# schema_electrica.net
KiCad netlist of a schematic drawn in EAGLE
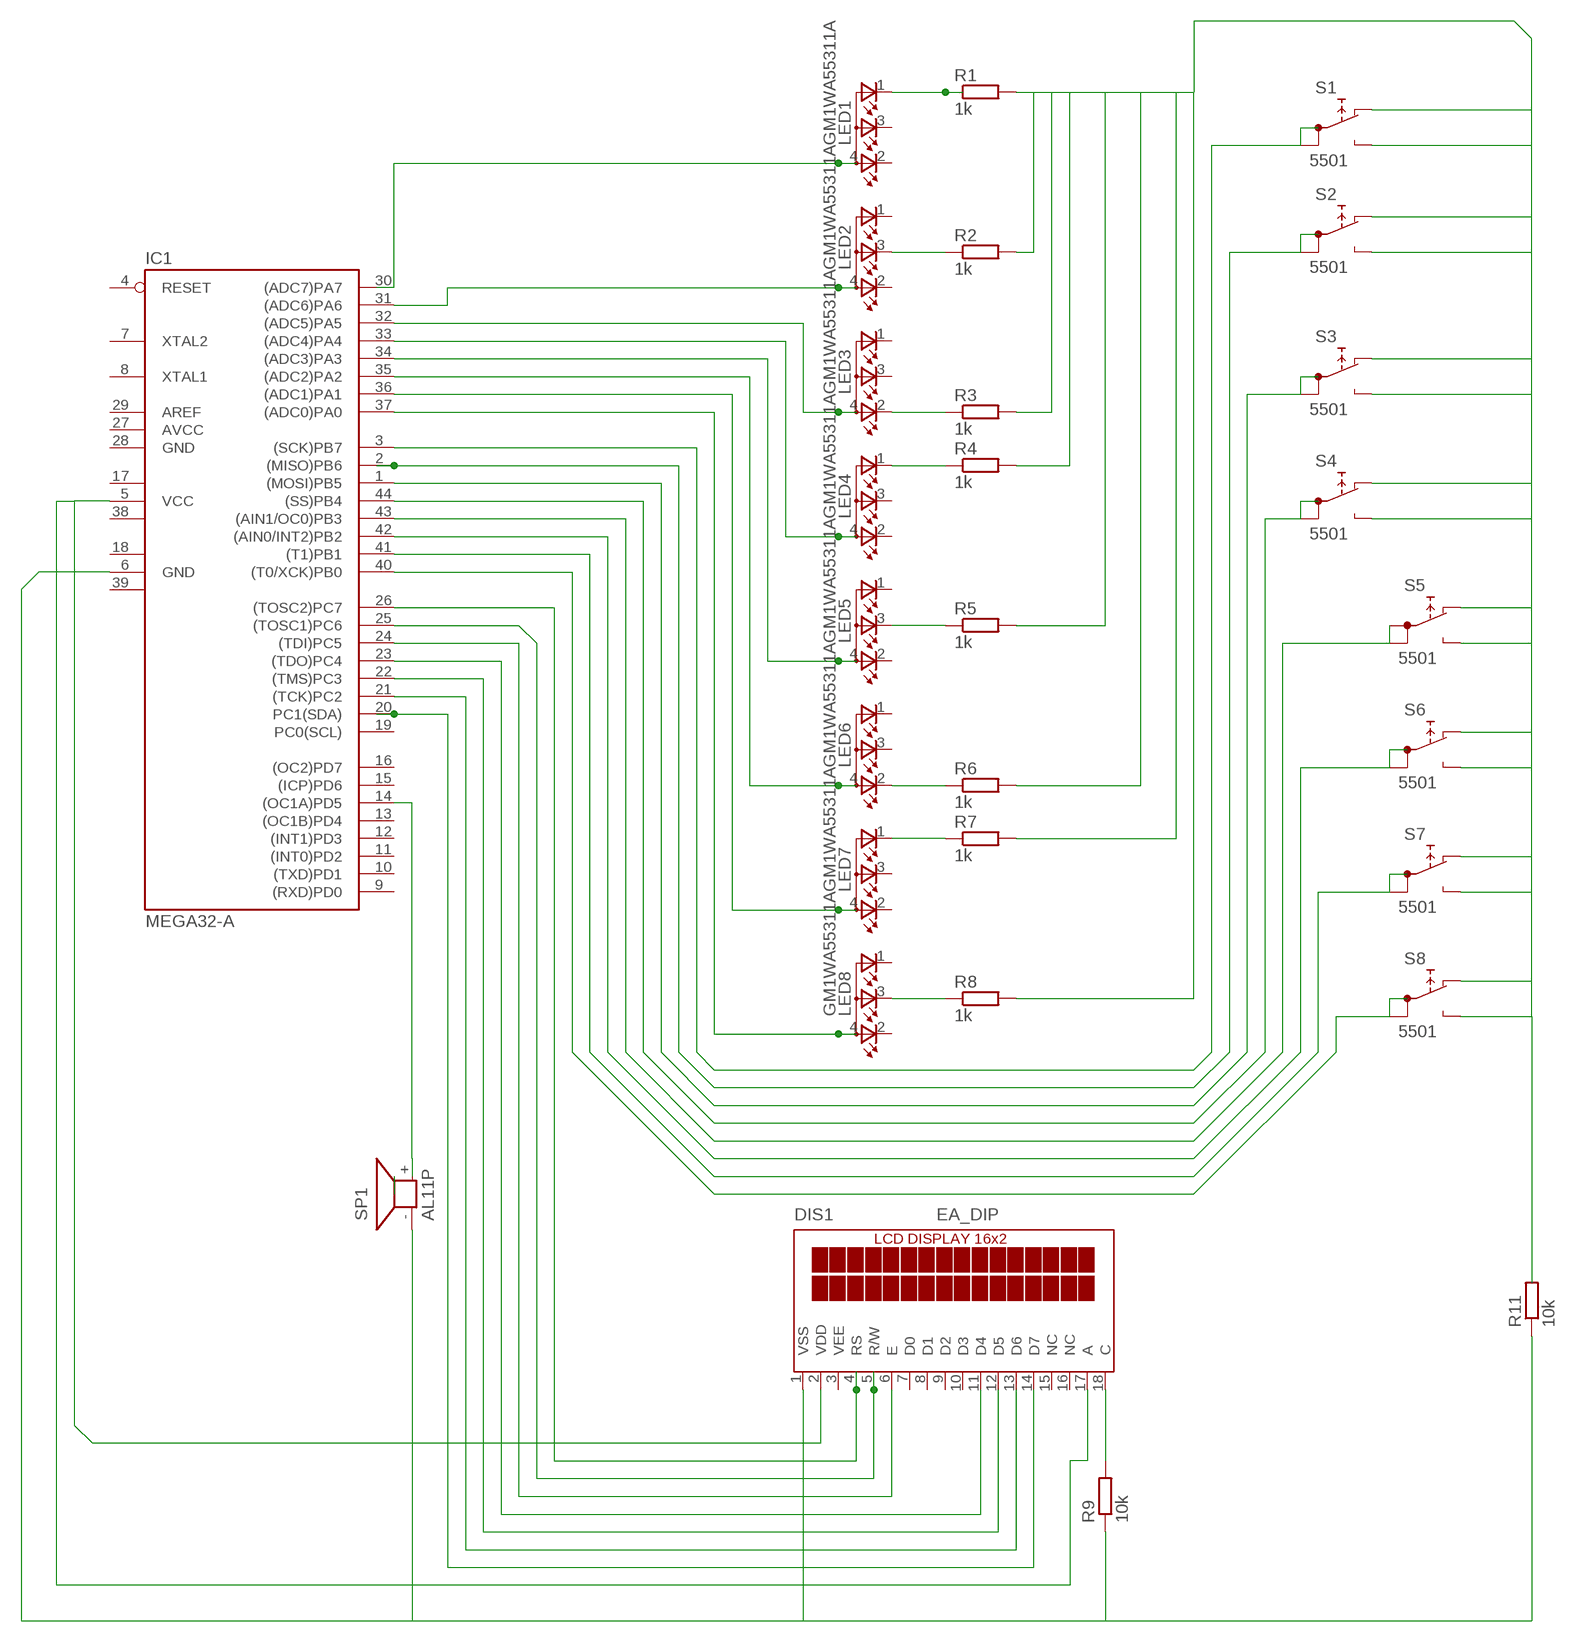
[diagram p0: schematic, sheet 1]

(export (version "E")
  (design (tool "Eeschema 10.0.6"))
  (components
    (comp (ref "DIS1")
      (value "EA_DIP")
      (footprint "eagle-import:EA_DIP")
      (libsource (lib "eagle-import") (part "EA_DIP"))
    )
    (comp (ref "IC1")
      (value "MEGA32-A")
      (footprint "eagle-import:TQFP44")
      (fields (field (name "MPN") "ATMEGA32-16AU"))
      (libsource (lib "eagle-import") (part "MEGA32-A"))
    )
    (comp (ref "LED1")
      (value "GM1WA55311A")
      (footprint "eagle-import:GM1WA55311A")
      (libsource (lib "eagle-import") (part "GM1WA55311A"))
    )
    (comp (ref "LED2")
      (value "GM1WA55311A")
      (footprint "eagle-import:GM1WA55311A")
      (libsource (lib "eagle-import") (part "GM1WA55311A"))
    )
    (comp (ref "LED3")
      (value "GM1WA55311A")
      (footprint "eagle-import:GM1WA55311A")
      (libsource (lib "eagle-import") (part "GM1WA55311A"))
    )
    (comp (ref "LED4")
      (value "GM1WA55311A")
      (footprint "eagle-import:GM1WA55311A")
      (libsource (lib "eagle-import") (part "GM1WA55311A"))
    )
    (comp (ref "LED5")
      (value "GM1WA55311A")
      (footprint "eagle-import:GM1WA55311A")
      (libsource (lib "eagle-import") (part "GM1WA55311A"))
    )
    (comp (ref "LED6")
      (value "GM1WA55311A")
      (footprint "eagle-import:GM1WA55311A")
      (libsource (lib "eagle-import") (part "GM1WA55311A"))
    )
    (comp (ref "LED7")
      (value "GM1WA55311A")
      (footprint "eagle-import:GM1WA55311A")
      (libsource (lib "eagle-import") (part "GM1WA55311A"))
    )
    (comp (ref "LED8")
      (value "GM1WA55311A")
      (footprint "eagle-import:GM1WA55311A")
      (libsource (lib "eagle-import") (part "GM1WA55311A"))
    )
    (comp (ref "R1")
      (value "1k")
      (footprint "eagle-import:VMTB60")
      (libsource (lib "eagle-import") (part "R-EU_VMTB60"))
    )
    (comp (ref "R2")
      (value "1k")
      (footprint "eagle-import:VMTB60")
      (libsource (lib "eagle-import") (part "R-EU_VMTB60"))
    )
    (comp (ref "R3")
      (value "1k")
      (footprint "eagle-import:VMTB60")
      (libsource (lib "eagle-import") (part "R-EU_VMTB60"))
    )
    (comp (ref "R4")
      (value "1k")
      (footprint "eagle-import:VMTB60")
      (libsource (lib "eagle-import") (part "R-EU_VMTB60"))
    )
    (comp (ref "R5")
      (value "1k")
      (footprint "eagle-import:VMTB60")
      (libsource (lib "eagle-import") (part "R-EU_VMTB60"))
    )
    (comp (ref "R6")
      (value "1k")
      (footprint "eagle-import:VMTB60")
      (libsource (lib "eagle-import") (part "R-EU_VMTB60"))
    )
    (comp (ref "R7")
      (value "1k")
      (footprint "eagle-import:VMTB60")
      (libsource (lib "eagle-import") (part "R-EU_VMTB60"))
    )
    (comp (ref "R8")
      (value "1k")
      (footprint "eagle-import:VMTB60")
      (libsource (lib "eagle-import") (part "R-EU_VMTB60"))
    )
    (comp (ref "R9")
      (value "10k")
      (footprint "eagle-import:0204V")
      (libsource (lib "eagle-import") (part "resistor_348_R-EU_0204/2V"))
    )
    (comp (ref "R11")
      (value "10k")
      (footprint "eagle-import:0204V")
      (libsource (lib "eagle-import") (part "resistor_348_R-EU_0204/2V"))
    )
    (comp (ref "S1")
      (value "5501")
      (footprint "eagle-import:5501")
      (libsource (lib "eagle-import") (part "55?01"))
    )
    (comp (ref "S2")
      (value "5501")
      (footprint "eagle-import:5501")
      (libsource (lib "eagle-import") (part "55?01"))
    )
    (comp (ref "S3")
      (value "5501")
      (footprint "eagle-import:5501")
      (libsource (lib "eagle-import") (part "55?01"))
    )
    (comp (ref "S4")
      (value "5501")
      (footprint "eagle-import:5501")
      (libsource (lib "eagle-import") (part "55?01"))
    )
    (comp (ref "S5")
      (value "5501")
      (footprint "eagle-import:5501")
      (libsource (lib "eagle-import") (part "55?01"))
    )
    (comp (ref "S6")
      (value "5501")
      (footprint "eagle-import:5501")
      (libsource (lib "eagle-import") (part "55?01"))
    )
    (comp (ref "S7")
      (value "5501")
      (footprint "eagle-import:5501")
      (libsource (lib "eagle-import") (part "55?01"))
    )
    (comp (ref "S8")
      (value "5501")
      (footprint "eagle-import:5501")
      (libsource (lib "eagle-import") (part "55?01"))
    )
    (comp (ref "SP1")
      (value "AL11P")
      (footprint "eagle-import:AL11P")
      (libsource (lib "eagle-import") (part "AL11P"))
    )
  )
  (nets
    (net (code "1") (name "/AVCC") (class "Default")
      (node (ref "IC1") (pin "27") (pinfunction "AVCC_27") (pintype "power_in"))
    )
    (net (code "2") (name "/GND") (class "Default")
      (node (ref "IC1") (pin "28") (pinfunction "GND_28") (pintype "power_in"))
    )
    (net (code "3") (name "/GND1") (class "Default")
      (node (ref "IC1") (pin "18") (pinfunction "GND1_18") (pintype "power_in"))
    )
    (net (code "4") (name "/GND2") (class "Default")
      (node (ref "IC1") (pin "39") (pinfunction "GND2_39") (pintype "power_in"))
    )
    (net (code "5") (name "/VCC1") (class "Default")
      (node (ref "IC1") (pin "17") (pinfunction "VCC1_17") (pintype "power_in"))
    )
    (net (code "6") (name "/VCC2") (class "Default")
      (node (ref "IC1") (pin "38") (pinfunction "VCC2_38") (pintype "power_in"))
    )
    (net (code "7") (name "/VEE") (class "Default")
      (node (ref "DIS1") (pin "3") (pinfunction "VEE_3") (pintype "power_in"))
    )
    (net (code "8") (name "Net-(DIS1-A)") (class "Default")
      (node (ref "DIS1") (pin "17") (pinfunction "A_17") (pintype "passive"))
      (node (ref "DIS1") (pin "2") (pinfunction "VDD_2") (pintype "power_in"))
      (node (ref "IC1") (pin "5") (pinfunction "VCC_5") (pintype "power_in"))
    )
    (net (code "9") (name "Net-(DIS1-C)") (class "Default")
      (node (ref "DIS1") (pin "18") (pinfunction "C_18") (pintype "passive"))
      (node (ref "R9") (pin "2") (pinfunction "2_2") (pintype "passive"))
    )
    (net (code "10") (name "Net-(DIS1-D4)") (class "Default")
      (node (ref "DIS1") (pin "11") (pinfunction "D4_11") (pintype "input"))
      (node (ref "IC1") (pin "23") (pinfunction "(TDO)PC4_23") (pintype "bidirectional"))
    )
    (net (code "11") (name "Net-(DIS1-D5)") (class "Default")
      (node (ref "DIS1") (pin "12") (pinfunction "D5_12") (pintype "input"))
      (node (ref "IC1") (pin "22") (pinfunction "(TMS)PC3_22") (pintype "bidirectional"))
    )
    (net (code "12") (name "Net-(DIS1-D6)") (class "Default")
      (node (ref "DIS1") (pin "13") (pinfunction "D6_13") (pintype "input"))
      (node (ref "IC1") (pin "21") (pinfunction "(TCK)PC2_21") (pintype "bidirectional"))
    )
    (net (code "13") (name "Net-(DIS1-D7)") (class "Default")
      (node (ref "DIS1") (pin "14") (pinfunction "D7_14") (pintype "input"))
      (node (ref "IC1") (pin "20") (pinfunction "PC1(SDA)_20") (pintype "bidirectional"))
    )
    (net (code "14") (name "Net-(DIS1-E)") (class "Default")
      (node (ref "DIS1") (pin "6") (pinfunction "E_6") (pintype "input"))
      (node (ref "IC1") (pin "24") (pinfunction "(TDI)PC5_24") (pintype "bidirectional"))
    )
    (net (code "15") (name "Net-(DIS1-RS)") (class "Default")
      (node (ref "DIS1") (pin "4") (pinfunction "RS_4") (pintype "input"))
      (node (ref "IC1") (pin "26") (pinfunction "(TOSC2)PC7_26") (pintype "bidirectional"))
    )
    (net (code "16") (name "Net-(DIS1-R{slash}W)") (class "Default")
      (node (ref "DIS1") (pin "5") (pinfunction "R/W_5") (pintype "input"))
      (node (ref "IC1") (pin "25") (pinfunction "(TOSC1)PC6_25") (pintype "bidirectional"))
    )
    (net (code "17") (name "Net-(DIS1-VSS)") (class "Default")
      (node (ref "DIS1") (pin "1") (pinfunction "VSS_1") (pintype "power_in"))
      (node (ref "IC1") (pin "6") (pinfunction "GND_6") (pintype "power_in"))
      (node (ref "R11") (pin "1") (pinfunction "1_1") (pintype "passive"))
      (node (ref "R9") (pin "1") (pinfunction "1_1") (pintype "passive"))
      (node (ref "SP1") (pin "-") (pinfunction "1_-") (pintype "passive"))
    )
    (net (code "18") (name "Net-(IC1-(ADC0)PA0)") (class "Default")
      (node (ref "IC1") (pin "37") (pinfunction "(ADC0)PA0_37") (pintype "bidirectional"))
      (node (ref "LED8") (pin "4") (pinfunction "A_4") (pintype "passive"))
    )
    (net (code "19") (name "Net-(IC1-(ADC1)PA1)") (class "Default")
      (node (ref "IC1") (pin "36") (pinfunction "(ADC1)PA1_36") (pintype "bidirectional"))
      (node (ref "LED7") (pin "4") (pinfunction "A_4") (pintype "passive"))
    )
    (net (code "20") (name "Net-(IC1-(ADC2)PA2)") (class "Default")
      (node (ref "IC1") (pin "35") (pinfunction "(ADC2)PA2_35") (pintype "bidirectional"))
      (node (ref "LED6") (pin "4") (pinfunction "A_4") (pintype "passive"))
    )
    (net (code "21") (name "Net-(IC1-(ADC3)PA3)") (class "Default")
      (node (ref "IC1") (pin "34") (pinfunction "(ADC3)PA3_34") (pintype "bidirectional"))
      (node (ref "LED5") (pin "4") (pinfunction "A_4") (pintype "passive"))
    )
    (net (code "22") (name "Net-(IC1-(ADC4)PA4)") (class "Default")
      (node (ref "IC1") (pin "33") (pinfunction "(ADC4)PA4_33") (pintype "bidirectional"))
      (node (ref "LED4") (pin "4") (pinfunction "A_4") (pintype "passive"))
    )
    (net (code "23") (name "Net-(IC1-(ADC5)PA5)") (class "Default")
      (node (ref "IC1") (pin "32") (pinfunction "(ADC5)PA5_32") (pintype "bidirectional"))
      (node (ref "LED3") (pin "4") (pinfunction "A_4") (pintype "passive"))
    )
    (net (code "24") (name "Net-(IC1-(ADC6)PA6)") (class "Default")
      (node (ref "IC1") (pin "31") (pinfunction "(ADC6)PA6_31") (pintype "bidirectional"))
      (node (ref "LED2") (pin "4") (pinfunction "A_4") (pintype "passive"))
    )
    (net (code "25") (name "Net-(IC1-(ADC7)PA7)") (class "Default")
      (node (ref "IC1") (pin "30") (pinfunction "(ADC7)PA7_30") (pintype "bidirectional"))
      (node (ref "LED1") (pin "4") (pinfunction "A_4") (pintype "passive"))
    )
    (net (code "26") (name "Net-(IC1-(AIN0{slash}INT2)PB2)") (class "Default")
      (node (ref "IC1") (pin "42") (pinfunction "(AIN0/INT2)PB2_42") (pintype "bidirectional"))
      (node (ref "S6") (pin "1A") (pinfunction "1A_1A") (pintype "passive"))
      (node (ref "S6") (pin "1B") (pinfunction "1B_1B") (pintype "passive"))
    )
    (net (code "27") (name "Net-(IC1-(AIN1{slash}OC0)PB3)") (class "Default")
      (node (ref "IC1") (pin "43") (pinfunction "(AIN1/OC0)PB3_43") (pintype "bidirectional"))
      (node (ref "S5") (pin "1A") (pinfunction "1A_1A") (pintype "passive"))
      (node (ref "S5") (pin "1B") (pinfunction "1B_1B") (pintype "passive"))
    )
    (net (code "28") (name "Net-(IC1-(MISO)PB6)") (class "Default")
      (node (ref "IC1") (pin "2") (pinfunction "(MISO)PB6_2") (pintype "bidirectional"))
      (node (ref "S2") (pin "1A") (pinfunction "1A_1A") (pintype "passive"))
      (node (ref "S2") (pin "1B") (pinfunction "1B_1B") (pintype "passive"))
    )
    (net (code "29") (name "Net-(IC1-(MOSI)PB5)") (class "Default")
      (node (ref "IC1") (pin "1") (pinfunction "(MOSI)PB5_1") (pintype "bidirectional"))
      (node (ref "S3") (pin "1A") (pinfunction "1A_1A") (pintype "passive"))
      (node (ref "S3") (pin "1B") (pinfunction "1B_1B") (pintype "passive"))
    )
    (net (code "30") (name "Net-(IC1-(OC1A)PD5)") (class "Default")
      (node (ref "IC1") (pin "14") (pinfunction "(OC1A)PD5_14") (pintype "bidirectional"))
      (node (ref "SP1") (pin "+") (pinfunction "2_+") (pintype "passive"))
    )
    (net (code "31") (name "Net-(IC1-(SCK)PB7)") (class "Default")
      (node (ref "IC1") (pin "3") (pinfunction "(SCK)PB7_3") (pintype "bidirectional"))
      (node (ref "S1") (pin "1A") (pinfunction "1A_1A") (pintype "passive"))
      (node (ref "S1") (pin "1B") (pinfunction "1B_1B") (pintype "passive"))
    )
    (net (code "32") (name "Net-(IC1-(SS)PB4)") (class "Default")
      (node (ref "IC1") (pin "44") (pinfunction "(SS)PB4_44") (pintype "bidirectional"))
      (node (ref "S4") (pin "1A") (pinfunction "1A_1A") (pintype "passive"))
      (node (ref "S4") (pin "1B") (pinfunction "1B_1B") (pintype "passive"))
    )
    (net (code "33") (name "Net-(IC1-(T0{slash}XCK)PB0)") (class "Default")
      (node (ref "IC1") (pin "40") (pinfunction "(T0/XCK)PB0_40") (pintype "bidirectional"))
      (node (ref "S8") (pin "1A") (pinfunction "1A_1A") (pintype "passive"))
      (node (ref "S8") (pin "1B") (pinfunction "1B_1B") (pintype "passive"))
    )
    (net (code "34") (name "Net-(IC1-(T1)PB1)") (class "Default")
      (node (ref "IC1") (pin "41") (pinfunction "(T1)PB1_41") (pintype "bidirectional"))
      (node (ref "S7") (pin "1A") (pinfunction "1A_1A") (pintype "passive"))
      (node (ref "S7") (pin "1B") (pinfunction "1B_1B") (pintype "passive"))
    )
    (net (code "35") (name "Net-(LED1-CGREEN)") (class "Default")
      (node (ref "LED1") (pin "1") (pinfunction "CGREEN_1") (pintype "passive"))
      (node (ref "R1") (pin "1") (pinfunction "1_1") (pintype "passive"))
    )
    (net (code "36") (name "Net-(LED2-CBLUE)") (class "Default")
      (node (ref "LED2") (pin "3") (pinfunction "CBLUE_3") (pintype "passive"))
      (node (ref "R2") (pin "1") (pinfunction "1_1") (pintype "passive"))
    )
    (net (code "37") (name "Net-(LED3-CRED)") (class "Default")
      (node (ref "LED3") (pin "2") (pinfunction "CRED_2") (pintype "passive"))
      (node (ref "R3") (pin "1") (pinfunction "1_1") (pintype "passive"))
    )
    (net (code "38") (name "Net-(LED4-CGREEN)") (class "Default")
      (node (ref "LED4") (pin "1") (pinfunction "CGREEN_1") (pintype "passive"))
      (node (ref "R4") (pin "1") (pinfunction "1_1") (pintype "passive"))
    )
    (net (code "39") (name "Net-(LED5-CBLUE)") (class "Default")
      (node (ref "LED5") (pin "3") (pinfunction "CBLUE_3") (pintype "passive"))
      (node (ref "R5") (pin "1") (pinfunction "1_1") (pintype "passive"))
    )
    (net (code "40") (name "Net-(LED6-CRED)") (class "Default")
      (node (ref "LED6") (pin "2") (pinfunction "CRED_2") (pintype "passive"))
      (node (ref "R6") (pin "1") (pinfunction "1_1") (pintype "passive"))
    )
    (net (code "41") (name "Net-(LED7-CGREEN)") (class "Default")
      (node (ref "LED7") (pin "1") (pinfunction "CGREEN_1") (pintype "passive"))
      (node (ref "R7") (pin "1") (pinfunction "1_1") (pintype "passive"))
    )
    (net (code "42") (name "Net-(LED8-CBLUE)") (class "Default")
      (node (ref "LED8") (pin "3") (pinfunction "CBLUE_3") (pintype "passive"))
      (node (ref "R8") (pin "1") (pinfunction "1_1") (pintype "passive"))
    )
    (net (code "43") (name "Net-(R1-Pad2)") (class "Default")
      (node (ref "R1") (pin "2") (pinfunction "2_2") (pintype "passive"))
      (node (ref "R11") (pin "2") (pinfunction "2_2") (pintype "passive"))
      (node (ref "R2") (pin "2") (pinfunction "2_2") (pintype "passive"))
      (node (ref "R3") (pin "2") (pinfunction "2_2") (pintype "passive"))
      (node (ref "R4") (pin "2") (pinfunction "2_2") (pintype "passive"))
      (node (ref "R5") (pin "2") (pinfunction "2_2") (pintype "passive"))
      (node (ref "R6") (pin "2") (pinfunction "2_2") (pintype "passive"))
      (node (ref "R7") (pin "2") (pinfunction "2_2") (pintype "passive"))
      (node (ref "R8") (pin "2") (pinfunction "2_2") (pintype "passive"))
      (node (ref "S1") (pin "NC") (pinfunction "NC_NC") (pintype "passive"))
      (node (ref "S1") (pin "NO") (pinfunction "NO_NO") (pintype "passive"))
      (node (ref "S2") (pin "NC") (pinfunction "NC_NC") (pintype "passive"))
      (node (ref "S2") (pin "NO") (pinfunction "NO_NO") (pintype "passive"))
      (node (ref "S3") (pin "NC") (pinfunction "NC_NC") (pintype "passive"))
      (node (ref "S3") (pin "NO") (pinfunction "NO_NO") (pintype "passive"))
      (node (ref "S4") (pin "NC") (pinfunction "NC_NC") (pintype "passive"))
      (node (ref "S4") (pin "NO") (pinfunction "NO_NO") (pintype "passive"))
      (node (ref "S5") (pin "NC") (pinfunction "NC_NC") (pintype "passive"))
      (node (ref "S5") (pin "NO") (pinfunction "NO_NO") (pintype "passive"))
      (node (ref "S6") (pin "NC") (pinfunction "NC_NC") (pintype "passive"))
      (node (ref "S6") (pin "NO") (pinfunction "NO_NO") (pintype "passive"))
      (node (ref "S7") (pin "NC") (pinfunction "NC_NC") (pintype "passive"))
      (node (ref "S7") (pin "NO") (pinfunction "NO_NO") (pintype "passive"))
      (node (ref "S8") (pin "NC") (pinfunction "NC_NC") (pintype "passive"))
      (node (ref "S8") (pin "NO") (pinfunction "NO_NO") (pintype "passive"))
    )
    (net (code "44") (name "unconnected-(DIS1-D0-Pad7)") (class "Default")
      (node (ref "DIS1") (pin "7") (pinfunction "D0_7") (pintype "input"))
    )
    (net (code "45") (name "unconnected-(DIS1-D1-Pad8)") (class "Default")
      (node (ref "DIS1") (pin "8") (pinfunction "D1_8") (pintype "input"))
    )
    (net (code "46") (name "unconnected-(DIS1-D2-Pad9)") (class "Default")
      (node (ref "DIS1") (pin "9") (pinfunction "D2_9") (pintype "input"))
    )
    (net (code "47") (name "unconnected-(DIS1-D3-Pad10)") (class "Default")
      (node (ref "DIS1") (pin "10") (pinfunction "D3_10") (pintype "input"))
    )
    (net (code "48") (name "unconnected-(DIS1-NC-Pad15)") (class "Default")
      (node (ref "DIS1") (pin "15") (pinfunction "NC_15") (pintype "no_connect"))
    )
    (net (code "49") (name "unconnected-(DIS1-NC-Pad16)") (class "Default")
      (node (ref "DIS1") (pin "16") (pinfunction "NC_16") (pintype "no_connect"))
    )
    (net (code "50") (name "unconnected-(IC1-(ICP)PD6-Pad15)") (class "Default")
      (node (ref "IC1") (pin "15") (pinfunction "(ICP)PD6_15") (pintype "bidirectional"))
    )
    (net (code "51") (name "unconnected-(IC1-(INT0)PD2-Pad11)") (class "Default")
      (node (ref "IC1") (pin "11") (pinfunction "(INT0)PD2_11") (pintype "bidirectional"))
    )
    (net (code "52") (name "unconnected-(IC1-(INT1)PD3-Pad12)") (class "Default")
      (node (ref "IC1") (pin "12") (pinfunction "(INT1)PD3_12") (pintype "bidirectional"))
    )
    (net (code "53") (name "unconnected-(IC1-(OC1B)PD4-Pad13)") (class "Default")
      (node (ref "IC1") (pin "13") (pinfunction "(OC1B)PD4_13") (pintype "bidirectional"))
    )
    (net (code "54") (name "unconnected-(IC1-(OC2)PD7-Pad16)") (class "Default")
      (node (ref "IC1") (pin "16") (pinfunction "(OC2)PD7_16") (pintype "bidirectional"))
    )
    (net (code "55") (name "unconnected-(IC1-(RXD)PD0-Pad9)") (class "Default")
      (node (ref "IC1") (pin "9") (pinfunction "(RXD)PD0_9") (pintype "bidirectional"))
    )
    (net (code "56") (name "unconnected-(IC1-(TXD)PD1-Pad10)") (class "Default")
      (node (ref "IC1") (pin "10") (pinfunction "(TXD)PD1_10") (pintype "bidirectional"))
    )
    (net (code "57") (name "unconnected-(IC1-AREF-Pad29)") (class "Default")
      (node (ref "IC1") (pin "29") (pinfunction "AREF_29") (pintype "passive"))
    )
    (net (code "58") (name "unconnected-(IC1-PC0(SCL)-Pad19)") (class "Default")
      (node (ref "IC1") (pin "19") (pinfunction "PC0(SCL)_19") (pintype "bidirectional"))
    )
    (net (code "59") (name "unconnected-(IC1-RESET-Pad4)") (class "Default")
      (node (ref "IC1") (pin "4") (pinfunction "RESET_4") (pintype "input"))
    )
    (net (code "60") (name "unconnected-(IC1-XTAL1-Pad8)") (class "Default")
      (node (ref "IC1") (pin "8") (pinfunction "XTAL1_8") (pintype "bidirectional"))
    )
    (net (code "61") (name "unconnected-(IC1-XTAL2-Pad7)") (class "Default")
      (node (ref "IC1") (pin "7") (pinfunction "XTAL2_7") (pintype "bidirectional"))
    )
    (net (code "62") (name "unconnected-(LED1-CBLUE-Pad3)") (class "Default")
      (node (ref "LED1") (pin "3") (pinfunction "CBLUE_3") (pintype "passive"))
    )
    (net (code "63") (name "unconnected-(LED1-CRED-Pad2)") (class "Default")
      (node (ref "LED1") (pin "2") (pinfunction "CRED_2") (pintype "passive"))
    )
    (net (code "64") (name "unconnected-(LED2-CGREEN-Pad1)") (class "Default")
      (node (ref "LED2") (pin "1") (pinfunction "CGREEN_1") (pintype "passive"))
    )
    (net (code "65") (name "unconnected-(LED2-CRED-Pad2)") (class "Default")
      (node (ref "LED2") (pin "2") (pinfunction "CRED_2") (pintype "passive"))
    )
    (net (code "66") (name "unconnected-(LED3-CBLUE-Pad3)") (class "Default")
      (node (ref "LED3") (pin "3") (pinfunction "CBLUE_3") (pintype "passive"))
    )
    (net (code "67") (name "unconnected-(LED3-CGREEN-Pad1)") (class "Default")
      (node (ref "LED3") (pin "1") (pinfunction "CGREEN_1") (pintype "passive"))
    )
    (net (code "68") (name "unconnected-(LED4-CBLUE-Pad3)") (class "Default")
      (node (ref "LED4") (pin "3") (pinfunction "CBLUE_3") (pintype "passive"))
    )
    (net (code "69") (name "unconnected-(LED4-CRED-Pad2)") (class "Default")
      (node (ref "LED4") (pin "2") (pinfunction "CRED_2") (pintype "passive"))
    )
    (net (code "70") (name "unconnected-(LED5-CGREEN-Pad1)") (class "Default")
      (node (ref "LED5") (pin "1") (pinfunction "CGREEN_1") (pintype "passive"))
    )
    (net (code "71") (name "unconnected-(LED5-CRED-Pad2)") (class "Default")
      (node (ref "LED5") (pin "2") (pinfunction "CRED_2") (pintype "passive"))
    )
    (net (code "72") (name "unconnected-(LED6-CBLUE-Pad3)") (class "Default")
      (node (ref "LED6") (pin "3") (pinfunction "CBLUE_3") (pintype "passive"))
    )
    (net (code "73") (name "unconnected-(LED6-CGREEN-Pad1)") (class "Default")
      (node (ref "LED6") (pin "1") (pinfunction "CGREEN_1") (pintype "passive"))
    )
    (net (code "74") (name "unconnected-(LED7-CBLUE-Pad3)") (class "Default")
      (node (ref "LED7") (pin "3") (pinfunction "CBLUE_3") (pintype "passive"))
    )
    (net (code "75") (name "unconnected-(LED7-CRED-Pad2)") (class "Default")
      (node (ref "LED7") (pin "2") (pinfunction "CRED_2") (pintype "passive"))
    )
    (net (code "76") (name "unconnected-(LED8-CGREEN-Pad1)") (class "Default")
      (node (ref "LED8") (pin "1") (pinfunction "CGREEN_1") (pintype "passive"))
    )
    (net (code "77") (name "unconnected-(LED8-CRED-Pad2)") (class "Default")
      (node (ref "LED8") (pin "2") (pinfunction "CRED_2") (pintype "passive"))
    )
  )
)
